# 15to3_3V.net
KiCad netlist of a schematic drawn in Altium Designer
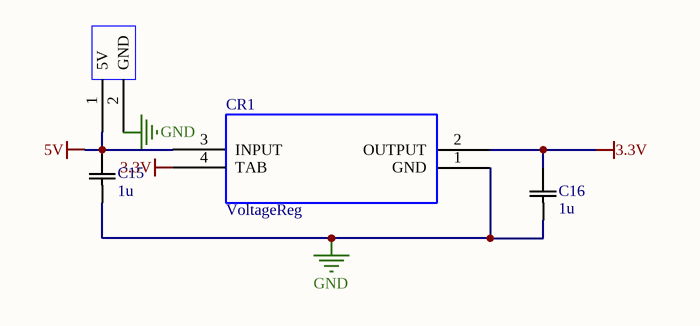
[diagram p0: 15to3.3V.SchDoc]

(export (version "E")
  (design (tool "Eeschema 10.0.6"))
  (components
    (comp (ref "C15")
      (value "1u")
      (footprint "Resistor1")
      (description "C0805C103J1GEC7800")
      (libsource (lib "PulseGenSymLib") (part "Capacitor1u"))
    )
    (comp (ref "C16")
      (value "1u")
      (footprint "Resistor1")
      (description "C0805C103J1GEC7800")
      (libsource (lib "PulseGenSymLib") (part "Capacitor1u"))
    )
    (comp (ref "CR1")
      (value "VoltageReg")
      (footprint "VoltageReg1")
      (description "LD1117S33TR")
      (libsource (lib "PulseGenSymLib") (part "VoltageReg"))
    )
    (comp (ref "U21") (value "Input") (footprint "Input") (libsource (lib "PulseGenSymLib") (part "Input")))
  )
  (nets
    (net (code "1") (name "3.3V") (class "Default")
      (node (ref "C16") (pin "2") (pinfunction "2_2") (pintype "passive"))
      (node (ref "CR1") (pin "2") (pinfunction "OUTPUT_2") (pintype "power_in"))
      (node (ref "CR1") (pin "4") (pinfunction "TAB_4") (pintype "power_in"))
    )
    (net (code "2") (name "5V") (class "Default")
      (node (ref "C15") (pin "2") (pinfunction "2_2") (pintype "passive"))
      (node (ref "CR1") (pin "3") (pinfunction "INPUT_3") (pintype "power_in"))
      (node (ref "U21") (pin "1") (pinfunction "5V_1") (pintype "passive"))
    )
    (net (code "3") (name "GND") (class "Default")
      (node (ref "C15") (pin "1") (pinfunction "1_1") (pintype "passive"))
      (node (ref "C16") (pin "1") (pinfunction "1_1") (pintype "passive"))
      (node (ref "CR1") (pin "1") (pinfunction "GND_1") (pintype "power_in"))
      (node (ref "U21") (pin "2") (pinfunction "GND_2") (pintype "passive"))
    )
  )
)
